# BikeLight.net
KiCad netlist of a schematic drawn in EAGLE
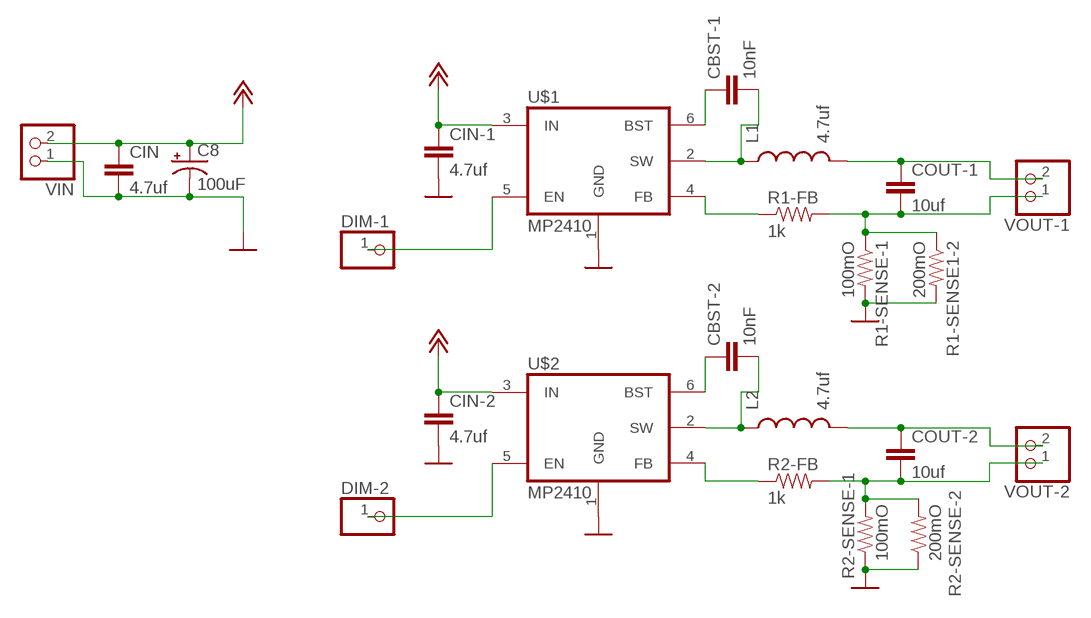
[diagram p0: schematic, sheet 1]

(export (version "E")
  (design (tool "Eeschema 10.0.6"))
  (components
    (comp (ref "C8")
      (value "100uF")
      (footprint "eagle-import:NIC_10X10.5_CAP")
      (libsource (lib "eagle-import") (part "100UF-POLAR-10X10.5-63V-20%"))
    )
    (comp (ref "CBST-1")
      (value "10nF")
      (footprint "eagle-import:0805")
      (libsource (lib "eagle-import") (part "CAP0805"))
    )
    (comp (ref "CBST-2")
      (value "10nF")
      (footprint "eagle-import:0805")
      (libsource (lib "eagle-import") (part "CAP0805"))
    )
    (comp (ref "CIN")
      (value "4.7uf")
      (footprint "eagle-import:1206")
      (libsource (lib "eagle-import") (part "CAP1206"))
    )
    (comp (ref "CIN-1")
      (value "4.7uf")
      (footprint "eagle-import:1206")
      (libsource (lib "eagle-import") (part "CAP1206"))
    )
    (comp (ref "CIN-2")
      (value "4.7uf")
      (footprint "eagle-import:1206")
      (libsource (lib "eagle-import") (part "CAP1206"))
    )
    (comp (ref "COUT-1")
      (value "10uf")
      (footprint "eagle-import:1210")
      (libsource (lib "eagle-import") (part "CAP1210"))
    )
    (comp (ref "COUT-2")
      (value "10uf")
      (footprint "eagle-import:1210")
      (libsource (lib "eagle-import") (part "CAP1210"))
    )
    (comp (ref "DIM-1")
      (value "PINHD-1X1")
      (footprint "eagle-import:1X01")
      (libsource (lib "eagle-import") (part "PINHD-1X1"))
    )
    (comp (ref "DIM-2")
      (value "PINHD-1X1")
      (footprint "eagle-import:1X01")
      (libsource (lib "eagle-import") (part "PINHD-1X1"))
    )
    (comp (ref "L1")
      (value "4.7uf")
      (footprint "eagle-import:RLB0912")
      (libsource (lib "eagle-import") (part "INDUCTORRLB0912"))
    )
    (comp (ref "L2")
      (value "4.7uf")
      (footprint "eagle-import:RLB0912")
      (libsource (lib "eagle-import") (part "INDUCTORRLB0912"))
    )
    (comp (ref "R1-FB")
      (value "1k")
      (footprint "eagle-import:0805")
      (libsource (lib "eagle-import") (part "RESISTOR0805-RES"))
    )
    (comp (ref "R1-SENSE-1")
      (value "100mO")
      (footprint "eagle-import:1206")
      (libsource (lib "eagle-import") (part "RESISTOR1206"))
    )
    (comp (ref "R1-SENSE1-2")
      (value "200mO")
      (footprint "eagle-import:1206")
      (libsource (lib "eagle-import") (part "RESISTOR1206"))
    )
    (comp (ref "R2-FB")
      (value "1k")
      (footprint "eagle-import:0805")
      (libsource (lib "eagle-import") (part "RESISTOR0805-RES"))
    )
    (comp (ref "R2-SENSE-1")
      (value "100mO")
      (footprint "eagle-import:1206")
      (libsource (lib "eagle-import") (part "RESISTOR1206"))
    )
    (comp (ref "R2-SENSE-2")
      (value "200mO")
      (footprint "eagle-import:1206")
      (libsource (lib "eagle-import") (part "RESISTOR1206"))
    )
    (comp (ref "U$1")
      (value "MP2410")
      (footprint "eagle-import:TSOT23-6")
      (libsource (lib "eagle-import") (part "MP2410"))
    )
    (comp (ref "U$2")
      (value "MP2410")
      (footprint "eagle-import:TSOT23-6")
      (libsource (lib "eagle-import") (part "MP2410"))
    )
    (comp (ref "VIN")
      (value "PINHD-1X2")
      (footprint "eagle-import:1X02")
      (libsource (lib "eagle-import") (part "PINHD-1X2"))
    )
    (comp (ref "VOUT-1")
      (value "PINHD-1X2")
      (footprint "eagle-import:1X02")
      (libsource (lib "eagle-import") (part "PINHD-1X2"))
    )
    (comp (ref "VOUT-2")
      (value "PINHD-1X2")
      (footprint "eagle-import:1X02")
      (libsource (lib "eagle-import") (part "PINHD-1X2"))
    )
  )
  (nets
    (net (code "1") (name "+12V") (class "Default")
      (node (ref "C8") (pin "+") (pinfunction "+_+") (pintype "passive"))
      (node (ref "CIN") (pin "1") (pinfunction "1_1") (pintype "passive"))
      (node (ref "CIN-1") (pin "1") (pinfunction "1_1") (pintype "passive"))
      (node (ref "CIN-2") (pin "1") (pinfunction "1_1") (pintype "passive"))
      (node (ref "U$1") (pin "3") (pinfunction "IN_3") (pintype "input"))
      (node (ref "U$2") (pin "3") (pinfunction "IN_3") (pintype "input"))
      (node (ref "VIN") (pin "2") (pinfunction "2_2") (pintype "passive"))
    )
    (net (code "2") (name "GND") (class "Default")
      (node (ref "C8") (pin "-") (pinfunction "-_-") (pintype "passive"))
      (node (ref "CIN") (pin "2") (pinfunction "2_2") (pintype "passive"))
      (node (ref "CIN-1") (pin "2") (pinfunction "2_2") (pintype "passive"))
      (node (ref "CIN-2") (pin "2") (pinfunction "2_2") (pintype "passive"))
      (node (ref "R1-SENSE-1") (pin "2") (pinfunction "2_2") (pintype "passive"))
      (node (ref "R1-SENSE1-2") (pin "2") (pinfunction "2_2") (pintype "passive"))
      (node (ref "R2-SENSE-1") (pin "1") (pinfunction "1_1") (pintype "passive"))
      (node (ref "R2-SENSE-2") (pin "1") (pinfunction "1_1") (pintype "passive"))
      (node (ref "U$1") (pin "1") (pinfunction "GND_1") (pintype "input"))
      (node (ref "U$2") (pin "1") (pinfunction "GND_1") (pintype "input"))
      (node (ref "VIN") (pin "1") (pinfunction "1_1") (pintype "passive"))
    )
    (net (code "3") (name "Net-(COUT-1-Pad1)") (class "Default")
      (node (ref "COUT-1") (pin "1") (pinfunction "1_1") (pintype "passive"))
      (node (ref "L1") (pin "2") (pinfunction "2_2") (pintype "passive"))
      (node (ref "VOUT-1") (pin "2") (pinfunction "2_2") (pintype "passive"))
    )
    (net (code "4") (name "Net-(COUT-1-Pad2)") (class "Default")
      (node (ref "COUT-1") (pin "2") (pinfunction "2_2") (pintype "passive"))
      (node (ref "R1-FB") (pin "2") (pinfunction "2_2") (pintype "passive"))
      (node (ref "R1-SENSE-1") (pin "1") (pinfunction "1_1") (pintype "passive"))
      (node (ref "R1-SENSE1-2") (pin "1") (pinfunction "1_1") (pintype "passive"))
      (node (ref "VOUT-1") (pin "1") (pinfunction "1_1") (pintype "passive"))
    )
    (net (code "5") (name "Net-(COUT-2-Pad1)") (class "Default")
      (node (ref "COUT-2") (pin "1") (pinfunction "1_1") (pintype "passive"))
      (node (ref "L2") (pin "2") (pinfunction "2_2") (pintype "passive"))
      (node (ref "VOUT-2") (pin "2") (pinfunction "2_2") (pintype "passive"))
    )
    (net (code "6") (name "Net-(COUT-2-Pad2)") (class "Default")
      (node (ref "COUT-2") (pin "2") (pinfunction "2_2") (pintype "passive"))
      (node (ref "R2-FB") (pin "2") (pinfunction "2_2") (pintype "passive"))
      (node (ref "R2-SENSE-1") (pin "2") (pinfunction "2_2") (pintype "passive"))
      (node (ref "R2-SENSE-2") (pin "2") (pinfunction "2_2") (pintype "passive"))
      (node (ref "VOUT-2") (pin "1") (pinfunction "1_1") (pintype "passive"))
    )
    (net (code "7") (name "Net-(U$1-BST)") (class "Default")
      (node (ref "CBST-1") (pin "1") (pinfunction "1_1") (pintype "passive"))
      (node (ref "U$1") (pin "6") (pinfunction "BST_6") (pintype "output"))
    )
    (net (code "8") (name "Net-(U$1-EN)") (class "Default")
      (node (ref "DIM-1") (pin "1") (pinfunction "1_1") (pintype "passive"))
      (node (ref "U$1") (pin "5") (pinfunction "EN_5") (pintype "input"))
    )
    (net (code "9") (name "Net-(U$1-FB)") (class "Default")
      (node (ref "R1-FB") (pin "1") (pinfunction "1_1") (pintype "passive"))
      (node (ref "U$1") (pin "4") (pinfunction "FB_4") (pintype "input"))
    )
    (net (code "10") (name "Net-(U$1-SW)") (class "Default")
      (node (ref "CBST-1") (pin "2") (pinfunction "2_2") (pintype "passive"))
      (node (ref "L1") (pin "1") (pinfunction "1_1") (pintype "passive"))
      (node (ref "U$1") (pin "2") (pinfunction "SW_2") (pintype "output"))
    )
    (net (code "11") (name "Net-(U$2-BST)") (class "Default")
      (node (ref "CBST-2") (pin "1") (pinfunction "1_1") (pintype "passive"))
      (node (ref "U$2") (pin "6") (pinfunction "BST_6") (pintype "output"))
    )
    (net (code "12") (name "Net-(U$2-EN)") (class "Default")
      (node (ref "DIM-2") (pin "1") (pinfunction "1_1") (pintype "passive"))
      (node (ref "U$2") (pin "5") (pinfunction "EN_5") (pintype "input"))
    )
    (net (code "13") (name "Net-(U$2-FB)") (class "Default")
      (node (ref "R2-FB") (pin "1") (pinfunction "1_1") (pintype "passive"))
      (node (ref "U$2") (pin "4") (pinfunction "FB_4") (pintype "input"))
    )
    (net (code "14") (name "Net-(U$2-SW)") (class "Default")
      (node (ref "CBST-2") (pin "2") (pinfunction "2_2") (pintype "passive"))
      (node (ref "L2") (pin "1") (pinfunction "1_1") (pintype "passive"))
      (node (ref "U$2") (pin "2") (pinfunction "SW_2") (pintype "output"))
    )
  )
)
